# RF.net
KiCad netlist of a schematic drawn in Altium Designer
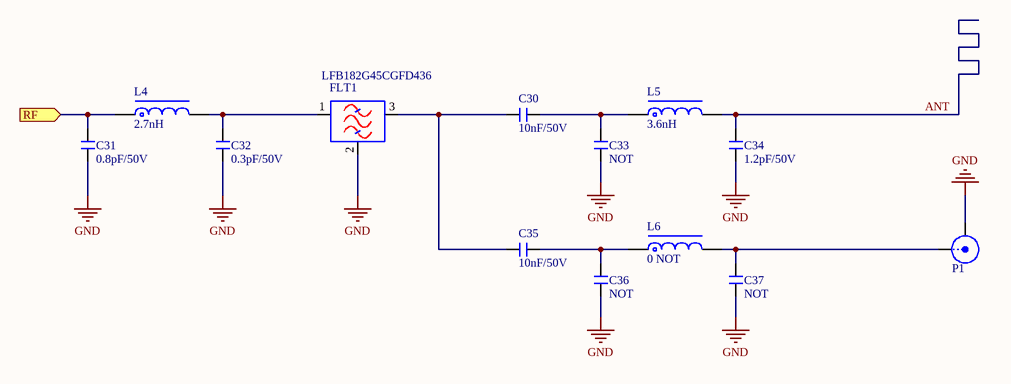
[diagram p0: RF.SchDoc]

(export (version "E")
  (design (tool "Eeschema 10.0.6"))
  (components
    (comp (ref "C30")
      (value "10nF/50V")
      (footprint "C 0402_L")
      (description "贴片电容")
      (libsource (lib "3.1   - 电阻-电容-电感") (part "C"))
    )
    (comp (ref "C31")
      (value "0.8pF/50V")
      (footprint "C 0402_L")
      (description "贴片电容")
      (libsource (lib "3.1   - 电阻-电容-电感") (part "C"))
    )
    (comp (ref "C32")
      (value "0.3pF/50V")
      (footprint "C 0402_L")
      (description "贴片电容")
      (libsource (lib "3.1   - 电阻-电容-电感") (part "C"))
    )
    (comp (ref "C33")
      (value "NOT")
      (footprint "C 0402_L")
      (description "贴片电容")
      (libsource (lib "3.1   - 电阻-电容-电感") (part "C"))
    )
    (comp (ref "C34")
      (value "1.2pF/50V")
      (footprint "C 0402_L")
      (description "贴片电容")
      (libsource (lib "3.1   - 电阻-电容-电感") (part "C"))
    )
    (comp (ref "C35")
      (value "10nF/50V")
      (footprint "C 0402_L")
      (description "贴片电容")
      (libsource (lib "3.1   - 电阻-电容-电感") (part "C"))
    )
    (comp (ref "C36")
      (value "NOT")
      (footprint "C 0402_L")
      (description "贴片电容")
      (libsource (lib "3.1   - 电阻-电容-电感") (part "C"))
    )
    (comp (ref "C37")
      (value "NOT")
      (footprint "C 0402_L")
      (description "贴片电容")
      (libsource (lib "3.1   - 电阻-电容-电感") (part "C"))
    )
    (comp (ref "FLT1")
      (value "LFB182G45CGFD436")
      (footprint "LFB182G45CGFD436")
      (description "Band Pass Filter Murata LFB182G45CGFD436")
      (libsource (lib "Passive") (part "LFB182G45CGFD436"))
    )
    (comp (ref "L4")
      (value "2.7nH")
      (footprint "L 0402")
      (description "LQG15HS2N7S02")
      (libsource (lib "3.1   - 电阻-电容-电感") (part "L-CD"))
    )
    (comp (ref "L5")
      (value "3.6nH")
      (footprint "L 0402")
      (description "LQG15HS3N6S02")
      (libsource (lib "3.1   - 电阻-电容-电感") (part "L-CD"))
    )
    (comp (ref "L6") (value "0 NOT") (footprint "L 0402") (libsource (lib "3.1   - 电阻-电容-电感") (part "L-CD")))
    (comp (ref "P1")
      (value "SMB")
      (footprint "PCBComponent_1 - duplicate")
      (description "SMB Straight Connector")
      (libsource (lib "Miscellaneous Connectors") (part "SMB"))
    )
  )
  (nets
    (net (code "1") (name "/ANT") (class "Default")
      (node (ref "C34") (pin "1") (pinfunction "1_1") (pintype "passive"))
      (node (ref "L5") (pin "2") (pinfunction "2_2") (pintype "passive"))
    )
    (net (code "2") (name "/RF") (class "Default")
      (node (ref "C31") (pin "1") (pinfunction "1_1") (pintype "passive"))
      (node (ref "L4") (pin "1") (pinfunction "1_1") (pintype "passive"))
    )
    (net (code "3") (name "GND") (class "Default")
      (node (ref "C31") (pin "2") (pinfunction "2_2") (pintype "passive"))
      (node (ref "C32") (pin "2") (pinfunction "2_2") (pintype "passive"))
      (node (ref "C33") (pin "2") (pinfunction "2_2") (pintype "passive"))
      (node (ref "C34") (pin "2") (pinfunction "2_2") (pintype "passive"))
      (node (ref "C36") (pin "2") (pinfunction "2_2") (pintype "passive"))
      (node (ref "C37") (pin "2") (pinfunction "2_2") (pintype "passive"))
      (node (ref "FLT1") (pin "2") (pinfunction "GND_2") (pintype "passive"))
      (node (ref "P1") (pin "2") (pinfunction "Y_2") (pintype "passive"))
    )
    (net (code "4") (name "Net-(C30-Pad1)") (class "Default")
      (node (ref "C30") (pin "1") (pinfunction "1_1") (pintype "passive"))
      (node (ref "C35") (pin "1") (pinfunction "1_1") (pintype "passive"))
      (node (ref "FLT1") (pin "3") (pinfunction "I/O_3") (pintype "passive"))
    )
    (net (code "5") (name "Net-(C30-Pad2)") (class "Default")
      (node (ref "C30") (pin "2") (pinfunction "2_2") (pintype "passive"))
      (node (ref "C33") (pin "1") (pinfunction "1_1") (pintype "passive"))
      (node (ref "L5") (pin "1") (pinfunction "1_1") (pintype "passive"))
    )
    (net (code "6") (name "Net-(C32-Pad1)") (class "Default")
      (node (ref "C32") (pin "1") (pinfunction "1_1") (pintype "passive"))
      (node (ref "FLT1") (pin "1") (pinfunction "I/O_1") (pintype "passive"))
      (node (ref "L4") (pin "2") (pinfunction "2_2") (pintype "passive"))
    )
    (net (code "7") (name "Net-(C35-Pad2)") (class "Default")
      (node (ref "C35") (pin "2") (pinfunction "2_2") (pintype "passive"))
      (node (ref "C36") (pin "1") (pinfunction "1_1") (pintype "passive"))
      (node (ref "L6") (pin "1") (pinfunction "1_1") (pintype "passive"))
    )
    (net (code "8") (name "Net-(P1-X)") (class "Default")
      (node (ref "C37") (pin "1") (pinfunction "1_1") (pintype "passive"))
      (node (ref "L6") (pin "2") (pinfunction "2_2") (pintype "passive"))
      (node (ref "P1") (pin "1") (pinfunction "X_1") (pintype "passive"))
    )
  )
)
